# P04_POWER01.net
KiCad netlist of a schematic drawn in Altium Designer
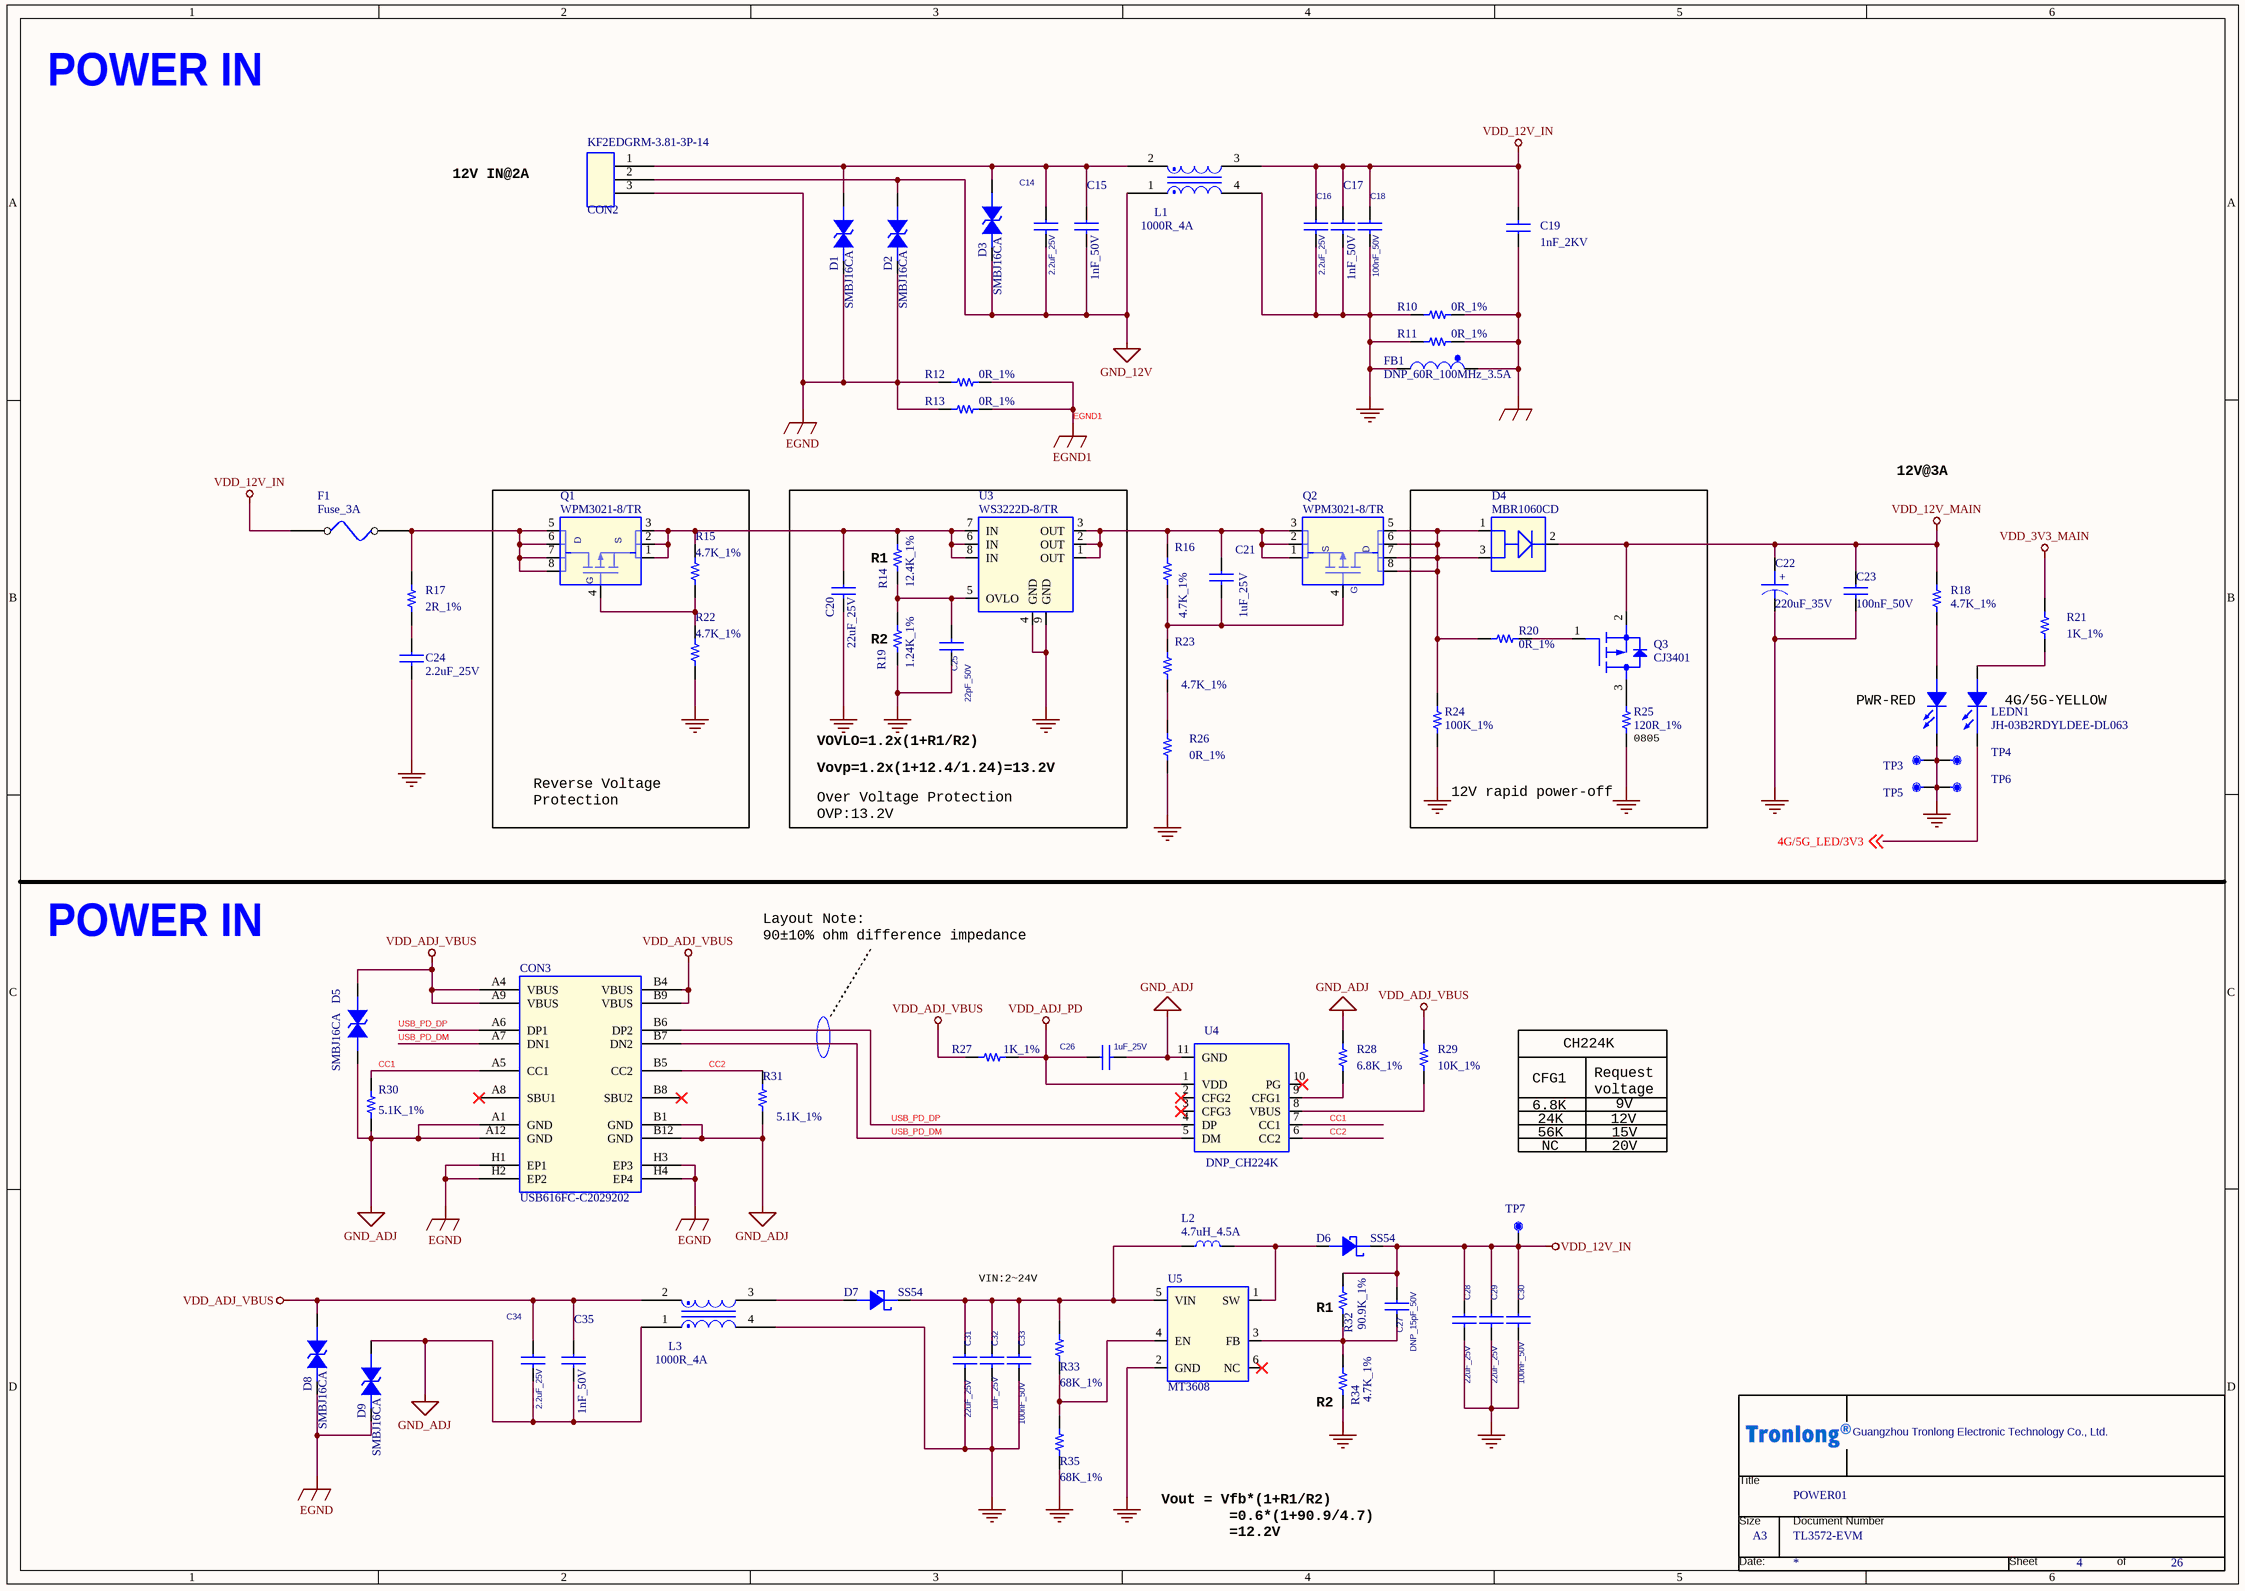
[diagram p0: P04_POWER01.SchDoc]

(export (version "E")
  (design (tool "Eeschema 10.0.6"))
  (components
    (comp (ref "C14")
      (value "2.2uF_25V")
      (footprint "C1206")
      (description "贴片陶瓷电容,2.2uF,10%,25V,X7R")
      (fields
        (field (name "MANUFACTURER") "广东风华高新科技股份有限公司（FH）")
        (field (name "MANUFACTURER PARTNUMBER") "1206B225K250NT")
      )
      (libsource (lib "*") (part "CAP NP_Dup2"))
    )
    (comp (ref "C15")
      (value "1nF_50V")
      (footprint "C0402")
      (description "贴片陶瓷电容,1nF,10%,50V,X7R")
      (fields
        (field (name "MANUFACTURER") "广东风华高新科技股份有限公司（FH）")
        (field (name "MANUFACTURER PARTNUMBER") "0402B102K500NT")
      )
      (libsource (lib "*") (part "CAP NP_Dup3"))
    )
    (comp (ref "C16")
      (value "2.2uF_25V")
      (footprint "C1206")
      (description "贴片陶瓷电容,2.2uF,10%,25V,X7R")
      (fields
        (field (name "MANUFACTURER") "广东风华高新科技股份有限公司（FH）")
        (field (name "MANUFACTURER PARTNUMBER") "1206B225K250NT")
      )
      (libsource (lib "*") (part "CAP NP_Dup2"))
    )
    (comp (ref "C17")
      (value "1nF_50V")
      (footprint "C0402")
      (description "贴片陶瓷电容,1nF,10%,50V,X7R")
      (fields
        (field (name "MANUFACTURER PARTNUMBER") "0402B102K500NT")
        (field (name "MANUFACTURER") "广东风华高新科技股份有限公司（FH）")
      )
      (libsource (lib "*") (part "CAP NP_Dup3"))
    )
    (comp (ref "C18")
      (value "100nF_50V")
      (footprint "C0402")
      (description "贴片陶瓷电容,100nF,10%,50V,X7R")
      (fields
        (field (name "MANUFACTURER PARTNUMBER") "0402B104K500NT")
        (field (name "MANUFACTURER") "广东风华高新科技股份有限公司（FH）")
      )
      (libsource (lib "*") (part "CAP_NP"))
    )
    (comp (ref "C19")
      (value "1nF_2KV")
      (footprint "C1206")
      (description "贴片陶瓷电容,1nF,10%,2KV,X7R")
      (fields
        (field (name "MANUFACTURER") "广东风华高新科技股份有限公司（FH）")
        (field (name "MANUFACTURER PARTNUMBER") "1206B102K202NT")
      )
      (libsource (lib "*") (part "CAP NP_Dup2"))
    )
    (comp (ref "C20")
      (value "22uF_25V")
      (footprint "C0805")
      (description "贴片陶瓷电容,22uF,20%,25V,X5R")
      (fields
        (field (name "MANUFACTURER") "广东风华高新科技股份有限公司（FH）")
        (field (name "MANUFACTURER PARTNUMBER") "0805X226M250NT")
      )
      (libsource (lib "*") (part "CAP NP_Dup2"))
    )
    (comp (ref "C21")
      (value "1uF_25V")
      (footprint "C0402")
      (description "贴片陶瓷电容,1uF,10%,25V,X5R")
      (fields
        (field (name "MANUFACTURER PARTNUMBER") "0402X105K250NT")
        (field (name "MANUFACTURER") "广东风华高新科技股份有限公司（FH）")
      )
      (libsource (lib "*") (part "CAP NP_Dup2"))
    )
    (comp (ref "C22")
      (value "220uF_35V")
      (footprint "cap_alu_smd_8x10d5")
      (description "贴片式铝电解电容,220uF,20%,35V")
      (fields
        (field (name "MANUFACTURER PARTNUMBER") "RVT1V221M0810VG")
        (field (name "MANUFACTURER") "东莞市合粤电子有限公司（Heyue）")
      )
      (libsource (lib "*") (part "CAP POL_Dup1"))
    )
    (comp (ref "C23")
      (value "100nF_50V")
      (footprint "C0402")
      (description "贴片陶瓷电容,100nF,10%,50V,X7R")
      (fields
        (field (name "MANUFACTURER PARTNUMBER") "0402B104K500NT")
        (field (name "MANUFACTURER") "广东风华高新科技股份有限公司（FH）")
      )
      (libsource (lib "*") (part "CAP NP_Dup2"))
    )
    (comp (ref "C24")
      (value "2.2uF_25V")
      (footprint "C1206")
      (description "贴片陶瓷电容,2.2uF,10%,25V,X7R")
      (fields
        (field (name "MANUFACTURER") "广东风华高新科技股份有限公司（FH）")
        (field (name "MANUFACTURER PARTNUMBER") "1206B225K250NT")
      )
      (libsource (lib "*") (part "CAP NP_Dup2"))
    )
    (comp (ref "C25")
      (value "22pF_50V")
      (footprint "C0603")
      (description "贴片陶瓷电容,22pF,5%,50V,COG")
      (fields
        (field (name "MANUFACTURER PARTNUMBER") "0603CG220J500NT")
        (field (name "MANUFACTURER") "广东风华高新科技股份有限公司（FH）")
      )
      (libsource (lib "*") (part "CAP NP_Dup2"))
    )
    (comp (ref "C26")
      (value "1uF_25V")
      (footprint "C0402")
      (description "贴片陶瓷电容,1uF,10%,25V,X5R")
      (fields
        (field (name "MANUFACTURER PARTNUMBER") "0402X105K250NT")
        (field (name "MANUFACTURER") "广东风华高新科技股份有限公司（FH）")
      )
      (libsource (lib "*") (part "CAP NP_Dup2"))
    )
    (comp (ref "C27")
      (value "DNP_15pF_50V")
      (footprint "C0402")
      (description "贴片陶瓷电容,15pF,5%,50V,COG")
      (fields
        (field (name "MANUFACTURER") "广东风华高新科技股份有限公司（FH）")
        (field (name "MANUFACTURER PARTNUMBER") "0402CG150J500NT")
      )
      (libsource (lib "*") (part "CAP NP_Dup2"))
    )
    (comp (ref "C28")
      (value "22uF_25V")
      (footprint "C0805")
      (description "贴片陶瓷电容,22uF,20%,25V,X5R")
      (fields
        (field (name "MANUFACTURER") "广东风华高新科技股份有限公司（FH）")
        (field (name "MANUFACTURER PARTNUMBER") "0805X226M250NT")
      )
      (libsource (lib "*") (part "CAP NP_Dup2"))
    )
    (comp (ref "C29")
      (value "22uF_25V")
      (footprint "C0805")
      (description "贴片陶瓷电容,22uF,20%,25V,X5R")
      (fields
        (field (name "MANUFACTURER") "广东风华高新科技股份有限公司（FH）")
        (field (name "MANUFACTURER PARTNUMBER") "0805X226M250NT")
      )
      (libsource (lib "*") (part "CAP NP_Dup2"))
    )
    (comp (ref "C30")
      (value "100nF_50V")
      (footprint "C0402")
      (description "贴片陶瓷电容,100nF,10%,50V,X7R")
      (fields
        (field (name "MANUFACTURER") "广东风华高新科技股份有限公司（FH）")
        (field (name "MANUFACTURER PARTNUMBER") "0402B104K500NT")
      )
      (libsource (lib "*") (part "CAP NP_Dup2"))
    )
    (comp (ref "C31")
      (value "22uF_25V")
      (footprint "C0805")
      (description "贴片陶瓷电容,22uF,20%,25V,X5R")
      (fields
        (field (name "MANUFACTURER") "广东风华高新科技股份有限公司（FH）")
        (field (name "MANUFACTURER PARTNUMBER") "0805X226M250NT")
      )
      (libsource (lib "*") (part "CAP NP_Dup2"))
    )
    (comp (ref "C32")
      (value "1uF_25V")
      (footprint "C0402")
      (description "贴片陶瓷电容,1uF,10%,25V,X5R")
      (fields
        (field (name "MANUFACTURER PARTNUMBER") "0402X105K250NT")
        (field (name "MANUFACTURER") "广东风华高新科技股份有限公司（FH）")
      )
      (libsource (lib "*") (part "CAP NP_Dup2"))
    )
    (comp (ref "C33")
      (value "100nF_50V")
      (footprint "C0402")
      (description "贴片陶瓷电容,100nF,10%,50V,X7R")
      (fields
        (field (name "MANUFACTURER PARTNUMBER") "0402B104K500NT")
        (field (name "MANUFACTURER") "广东风华高新科技股份有限公司（FH）")
      )
      (libsource (lib "*") (part "CAP NP_Dup2"))
    )
    (comp (ref "C34")
      (value "2.2uF_25V")
      (footprint "C1206")
      (description "贴片陶瓷电容,2.2uF,10%,25V,X7R")
      (fields
        (field (name "MANUFACTURER") "广东风华高新科技股份有限公司（FH）")
        (field (name "MANUFACTURER PARTNUMBER") "1206B225K250NT")
      )
      (libsource (lib "*") (part "CAP NP_Dup2"))
    )
    (comp (ref "C35")
      (value "1nF_50V")
      (footprint "C0402")
      (description "贴片陶瓷电容,1nF,10%,50V,X7R")
      (fields
        (field (name "MANUFACTURER") "广东风华高新科技股份有限公司（FH）")
        (field (name "MANUFACTURER PARTNUMBER") "0402B102K500NT")
      )
      (libsource (lib "*") (part "CAP NP_Dup3"))
    )
    (comp (ref "CON2")
      (value "KF2EDGRM-3.81-3P-14")
      (footprint "CON_3P_3D81_90_MALE_A")
      (description "插拔式端子座,1x3P,3.81mm,90度,带法兰")
      (fields (field (name "MANUFACTURER") "慈溪市科发电子有限公司（KEFA）"))
      (libsource (lib "*") (part "CON3_Dup1"))
    )
    (comp (ref "CON3")
      (value "USB616FC-C2029202")
      (footprint "TYPE-C_16P_180_SMD")
      (description "Type-C座,16P,0.8mm,母座,侧贴")
      (fields (field (name "MANUFACTURER") "深圳市爱特姆科技有限公司（ATOM）"))
      (libsource (lib "*") (part "usb 3_0.0 type-c female"))
    )
    (comp (ref "D1")
      (value "SMBJ16CA")
      (footprint "SMB")
      (description "TVS二极管,VRWM=16V,VBR=17.8V,一组,双向")
      (fields (field (name "MANUFACTURER") "江苏长晶科技有限公司（JSCJ）"))
      (libsource (lib "*") (part "DIODE-TRIG"))
    )
    (comp (ref "D2")
      (value "SMBJ16CA")
      (footprint "SMB")
      (description "TVS二极管,VRWM=16V,VBR=17.8V,一组,双向")
      (fields (field (name "MANUFACTURER") "江苏长晶科技有限公司（JSCJ）"))
      (libsource (lib "*") (part "DIODE-TRIG"))
    )
    (comp (ref "D3")
      (value "SMBJ16CA")
      (footprint "SMB")
      (description "TVS二极管,VRWM=16V,VBR=17.8V,一组,双向")
      (fields (field (name "MANUFACTURER") "江苏长晶科技有限公司（JSCJ）"))
      (libsource (lib "*") (part "DIODE-TRIG"))
    )
    (comp (ref "D4")
      (value "MBR1060CD")
      (footprint "TO-252")
      (description "肖特基二极管,VR=60V,IF=10A,VF=0.75V@5A,两路")
      (fields (field (name "MANUFACTURER") "山东芯诺电子科技股份有限公司（xnelec）"))
      (libsource (lib "*") (part "MBRB1045_0"))
    )
    (comp (ref "D5")
      (value "SMBJ16CA")
      (footprint "SMB")
      (description "TVS二极管,VRWM=16V,VBR=17.8V,一组,双向")
      (fields (field (name "MANUFACTURER") "江苏长晶科技股份有限公司（JSCJ）"))
      (libsource (lib "*") (part "DIODE-TRIG"))
    )
    (comp (ref "D6")
      (value "SS54")
      (footprint "SMA")
      (description "肖特基二极管,VR=40V,IF=5A,VF=0.55V@5A")
      (fields (field (name "MANUFACTURER") "江苏长晶科技股份有限公司（JSCJ）"))
      (libsource (lib "*") (part "DIODE SCHOTTKY"))
    )
    (comp (ref "D7")
      (value "SS54")
      (footprint "SMA")
      (description "肖特基二极管,VR=40V,IF=5A,VF=0.55V@5A")
      (fields (field (name "MANUFACTURER") "江苏长晶科技股份有限公司（JSCJ）"))
      (libsource (lib "*") (part "DIODE SCHOTTKY"))
    )
    (comp (ref "D8")
      (value "SMBJ16CA")
      (footprint "SMB")
      (description "TVS二极管,VRWM=16V,VBR=17.8V,一组,双向")
      (fields (field (name "MANUFACTURER") "江苏长晶科技有限公司（JSCJ）"))
      (libsource (lib "*") (part "DIODE-TRIG"))
    )
    (comp (ref "D9")
      (value "SMBJ16CA")
      (footprint "SMB")
      (description "TVS二极管,VRWM=16V,VBR=17.8V,一组,双向")
      (fields (field (name "MANUFACTURER") "江苏长晶科技有限公司（JSCJ）"))
      (libsource (lib "*") (part "DIODE-TRIG"))
    )
    (comp (ref "F1")
      (value "Fuse_3A")
      (footprint "F1206")
      (description "保险丝，Vmax=72V,Imax=50A,Ihold=3A")
      (fields
        (field (name "MANUFACTURER") "东莞市竞沃电子科技有限公司（TLC）")
        (field (name "MANUFACTURER PARTNUMBER") "F12T3")
      )
      (libsource (lib "*") (part "FUSE"))
    )
    (comp (ref "FB1")
      (value "DNP_60R_100MHz_3.5A")
      (footprint "L0603")
      (description "磁珠,20mΩ,3.5A,60R@100MHz")
      (fields
        (field (name "MANUFACTURER") "TDK(日本东电化)")
        (field (name "MANUFACTURER PARTNUMBER") "MPZ1608S600ATAH0")
      )
      (libsource (lib "*") (part "FERRITE BEAD_Dup1"))
    )
    (comp (ref "L1")
      (value "1000R_4A")
      (footprint "SMD-L9070M-4P")
      (description "贴片共模电感,13mΩ,4A,50V,1000Ω@100MHz")
      (fields (field (name "MANUFACTURER") "深圳市宏业兴电子有限公司（HONGYEX）") (field (name "PART NUMBER") "G11.00002"))
      (libsource (lib "*") (part "ACM1211-701-2PL-TL01"))
    )
    (comp (ref "L2")
      (value "4.7uH_4.5A")
      (footprint "SMD-L5452M-2P")
      (description "贴片功率电感,4.7uH,0.060Ω,Isat=5A,Irms=4.5A")
      (fields
        (field (name "MANUFACTURER") "深圳市长江微电科技有限公司（Cjiang）")
        (field (name "MANUFACTURER PARTNUMBER") "FXL0530-4R7M")
      )
      (libsource (lib "*") (part "1211_CHOKE_0"))
    )
    (comp (ref "L3")
      (value "1000R_4A")
      (footprint "SMD-L9070M-4P")
      (description "贴片共模电感,13mΩ,4A,50V,1000Ω@100MHz")
      (fields (field (name "MANUFACTURER") "深圳市宏业兴电子有限公司（HONGYEX）") (field (name "PART NUMBER") "G11.00002"))
      (libsource (lib "*") (part "ACM1211-701-2PL-TL01"))
    )
    (comp (ref "LEDN1")
      (value "JH-03B2RDYLDEE-DL063")
      (footprint "led-th_4p-l12d8-w4d6")
      (description "直插式发光二极管,绿色,带灯座")
      (fields
        (field (name "MANUFACTURER") "深圳市巨弘光电有限公司（JUHLIGHT）")
        (field (name "MANUFACTURER PARTNUMBER") "JH-03B2YG1E-DL")
      )
      (libsource (lib "*") (part "LED_4"))
    )
    (comp (ref "Q1")
      (value "WPM3021-8/TR")
      (footprint "PSOPSOP-8L")
      (description "MOSFET,P沟道,VDSS=-30V,VGSS=±25V,ID=-13A,PD=3.8W,VGS(th)=-3V")
      (fields (field (name "MANUFACTURER") "上海韦尔半导体股份有限公司（WILLSEMI）"))
      (libsource (lib "") (part "WPM3021_1"))
    )
    (comp (ref "Q2")
      (value "WPM3021-8/TR")
      (footprint "PSOPSOP-8L")
      (description "MOSFET,P沟道,VDSS=-30V,VGSS=±25V,ID=-13A,PD=3.8W,VGS(th)=-3V")
      (fields (field (name "MANUFACTURER") "上海韦尔半导体股份有限公司（WILLSEMI）"))
      (libsource (lib "*") (part "WPM3021"))
    )
    (comp (ref "Q3")
      (value "CJ3401")
      (footprint "SOT23-3")
      (description "MOSFET,P沟道,VDSS=-30V,VGSS=±12V,ID=-4.2A,PD=0.35W,VGS(th)=-1.3V")
      (fields (field (name "MANUFACTURER") "江苏长晶科技股份有限公司（JSCJ）"))
      (libsource (lib "*") (part "MOSFET P SOT"))
    )
    (comp (ref "R10")
      (value "0R_1%")
      (footprint "R1206")
      (description "贴片电阻,0R,±1%,1/4W")
      (fields
        (field (name "MANUFACTURER PARTNUMBER") "RS-06000FT")
        (field (name "MANUFACTURER") "广东风华高新科技股份有限公司（FH）")
      )
      (libsource (lib "*") (part "Resistor_Dup3"))
    )
    (comp (ref "R11")
      (value "0R_1%")
      (footprint "R1206")
      (description "贴片电阻,0R,±1%,1/4W")
      (fields
        (field (name "MANUFACTURER PARTNUMBER") "RS-06000FT")
        (field (name "MANUFACTURER") "广东风华高新科技股份有限公司（FH）")
      )
      (libsource (lib "*") (part "Resistor_Dup3"))
    )
    (comp (ref "R12")
      (value "0R_1%")
      (footprint "R1206")
      (description "贴片电阻,0R,±1%,1/4W")
      (fields
        (field (name "MANUFACTURER") "广东风华高新科技股份有限公司（FH）")
        (field (name "MANUFACTURER PARTNUMBER") "RS-06000FT")
      )
      (libsource (lib "*") (part "Resistor_Dup3"))
    )
    (comp (ref "R13")
      (value "0R_1%")
      (footprint "R1206")
      (description "贴片电阻,0R,±1%,1/4W")
      (fields
        (field (name "MANUFACTURER PARTNUMBER") "RS-06000FT")
        (field (name "MANUFACTURER") "广东风华高新科技股份有限公司（FH）")
      )
      (libsource (lib "*") (part "Resistor_Dup3"))
    )
    (comp (ref "R14")
      (value "12.4K_1%")
      (footprint "R0402")
      (description "0402WGF1242TCE")
      (fields
        (field (name "MANUFACTURER PARTNUMBER") "12.4K,±1%,R0402,≥1/16W")
        (field (name "MANUFACTURER") "广州创龙")
      )
      (libsource (lib "*") (part "Resistor_Dup3"))
    )
    (comp (ref "R15")
      (value "4.7K_1%")
      (footprint "R0402")
      (description "贴片电阻,4.7K,±1%,1/16W")
      (fields
        (field (name "MANUFACTURER PARTNUMBER") "RC-02K4701FT")
        (field (name "MANUFACTURER") "广东风华高新科技股份有限公司（FH）")
      )
      (libsource (lib "*") (part "Resistor_Dup3"))
    )
    (comp (ref "R16")
      (value "4.7K_1%")
      (footprint "R0402")
      (description "贴片电阻,4.7K,±1%,1/16W")
      (fields
        (field (name "MANUFACTURER PARTNUMBER") "RC-02K4701FT")
        (field (name "MANUFACTURER") "广东风华高新科技股份有限公司（FH）")
      )
      (libsource (lib "*") (part "Resistor_Dup3"))
    )
    (comp (ref "R17")
      (value "2R_1%")
      (footprint "R1210")
      (description "贴片电阻,2R,±1%,1/3W")
      (fields
        (field (name "MANUFACTURER PARTNUMBER") "RS-1210L2R00FT")
        (field (name "MANUFACTURER") "广东风华高新科技股份有限公司（FH）")
      )
      (libsource (lib "*") (part "Resistor_Dup3"))
    )
    (comp (ref "R18")
      (value "4.7K_1%")
      (footprint "R0402")
      (description "贴片电阻,4.7K,±1%,1/16W")
      (fields
        (field (name "MANUFACTURER") "广东风华高新科技股份有限公司（FH）")
        (field (name "MANUFACTURER PARTNUMBER") "RC-02K4701FT")
      )
      (libsource (lib "*") (part "Resistor_Dup3"))
    )
    (comp (ref "R19")
      (value "1.24K_1%")
      (footprint "R0402")
      (description "贴片电阻,1.24K,±1%,1/16W")
      (fields
        (field (name "MANUFACTURER") "广东风华高新科技股份有限公司（FH）")
        (field (name "MANUFACTURER PARTNUMBER") "RC-02K1241FT")
      )
      (libsource (lib "*") (part "Resistor_Dup3"))
    )
    (comp (ref "R20")
      (value "0R_1%")
      (footprint "R0402")
      (description "贴片电阻,0R,±1%,1/16W")
      (fields
        (field (name "MANUFACTURER") "广东风华高新科技股份有限公司（FH）")
        (field (name "MANUFACTURER PARTNUMBER") "RC-02000FT")
      )
      (libsource (lib "*") (part "Resistor_Dup3"))
    )
    (comp (ref "R21")
      (value "1K_1%")
      (footprint "R0603")
      (description "贴片电阻,1K,±1%,1/10W")
      (fields
        (field (name "MANUFACTURER") "广东风华高新科技股份有限公司（FH）")
        (field (name "MANUFACTURER PARTNUMBER") "RS-03K1001FT")
      )
      (libsource (lib "*") (part "Resistor_Dup3"))
    )
    (comp (ref "R22")
      (value "4.7K_1%")
      (footprint "R0402")
      (description "贴片电阻,4.7K,±1%,1/16W")
      (fields
        (field (name "MANUFACTURER") "广东风华高新科技股份有限公司（FH）")
        (field (name "MANUFACTURER PARTNUMBER") "RC-02K4701FT")
      )
      (libsource (lib "*") (part "Resistor_Dup3"))
    )
    (comp (ref "R23")
      (value "4.7K_1%")
      (footprint "R0402")
      (description "贴片电阻,4.7K,±1%,1/16W")
      (fields
        (field (name "MANUFACTURER") "广东风华高新科技股份有限公司（FH）")
        (field (name "MANUFACTURER PARTNUMBER") "RC-02K4701FT")
      )
      (libsource (lib "*") (part "Resistor_Dup3"))
    )
    (comp (ref "R24")
      (value "100K_1%")
      (footprint "R0402")
      (description "RC0402FR-07100KL,0402WGF1003TCE")
      (fields
        (field (name "MANUFACTURER") "广州创龙")
        (field (name "MANUFACTURER PARTNUMBER") "100K,±1%,R0402,≥1/16W")
      )
      (libsource (lib "*") (part "Resistor_Dup3"))
    )
    (comp (ref "R25")
      (value "120R_1%")
      (footprint "R0805")
      (description "贴片电阻,120R,±1%,1/8W")
      (fields
        (field (name "MANUFACTURER") "广东风华高新科技股份有限公司（FH）")
        (field (name "MANUFACTURER PARTNUMBER") "RS-05K1200FT")
      )
      (libsource (lib "*") (part "Resistor_Dup3"))
    )
    (comp (ref "R26")
      (value "0R_1%")
      (footprint "R0402")
      (description "贴片电阻,0R,±1%,1/16W")
      (fields
        (field (name "MANUFACTURER") "广东风华高新科技股份有限公司（FH）")
        (field (name "MANUFACTURER PARTNUMBER") "RC-02000FT")
      )
      (libsource (lib "*") (part "Resistor_Dup3"))
    )
    (comp (ref "R27")
      (value "1K_1%")
      (footprint "R0805")
      (description "贴片电阻,1K,±1%,1/8W")
      (fields
        (field (name "MANUFACTURER PARTNUMBER") "RS-05K1001FT")
        (field (name "MANUFACTURER") "广东风华高新科技股份有限公司（FH）")
      )
      (libsource (lib "*") (part "Resistor_Dup3"))
    )
    (comp (ref "R28")
      (value "6.8K_1%")
      (footprint "R0402")
      (description "贴片电阻,6.8K,±1%,1/16W")
      (fields
        (field (name "MANUFACTURER") "广东风华高新科技股份有限公司（FH）")
        (field (name "MANUFACTURER PARTNUMBER") "RC-02K6801FT")
      )
      (libsource (lib "*") (part "Resistor_Dup3"))
    )
    (comp (ref "R29")
      (value "10K_1%")
      (footprint "R0402")
      (description "贴片电阻,10K,±1%,1/16W")
      (fields
        (field (name "MANUFACTURER") "广东风华高新科技股份有限公司（FH）")
        (field (name "MANUFACTURER PARTNUMBER") "RC-02K1002FT")
      )
      (libsource (lib "*") (part "Resistor_Dup3"))
    )
    (comp (ref "R30")
      (value "5.1K_1%")
      (footprint "R0402")
      (description "贴片电阻,5.1K,±1%,1/16W")
      (fields
        (field (name "MANUFACTURER") "广东风华高新科技股份有限公司（FH）")
        (field (name "MANUFACTURER PARTNUMBER") "RC-02K5101FT")
      )
      (libsource (lib "*") (part "Resistor_Dup3"))
    )
    (comp (ref "R31")
      (value "5.1K_1%")
      (footprint "R0402")
      (description "贴片电阻,5.1K,±1%,1/16W")
      (fields
        (field (name "MANUFACTURER") "广东风华高新科技股份有限公司（FH）")
        (field (name "MANUFACTURER PARTNUMBER") "RC-02K5101FT")
      )
      (libsource (lib "*") (part "Resistor_Dup3"))
    )
    (comp (ref "R32")
      (value "90.9K_1%")
      (footprint "R0402")
      (description "贴片电阻,90.9K,±1%,1/16W")
      (fields
        (field (name "MANUFACTURER") "广东风华高新科技股份有限公司（FH）")
        (field (name "MANUFACTURER PARTNUMBER") "RC-02K9092FT")
      )
      (libsource (lib "*") (part "Resistor_Dup3"))
    )
    (comp (ref "R33")
      (value "68K_1%")
      (footprint "R0402")
      (description "贴片电阻,68K,±1%,1/16W")
      (fields
        (field (name "MANUFACTURER PARTNUMBER") "RC-02K6802FT")
        (field (name "MANUFACTURER") "广东风华高新科技股份有限公司（FH）")
      )
      (libsource (lib "*") (part "Resistor_Dup3"))
    )
    (comp (ref "R34")
      (value "4.7K_1%")
      (footprint "R0402")
      (description "贴片电阻,4.7K,±1%,1/16W")
      (fields
        (field (name "MANUFACTURER PARTNUMBER") "RC-02K4701FT")
        (field (name "MANUFACTURER") "广东风华高新科技股份有限公司（FH）")
      )
      (libsource (lib "*") (part "Resistor_Dup3"))
    )
    (comp (ref "R35")
      (value "68K_1%")
      (footprint "R0402")
      (description "贴片电阻,68K,±1%,1/16W")
      (fields
        (field (name "MANUFACTURER") "广东风华高新科技股份有限公司（FH）")
        (field (name "MANUFACTURER PARTNUMBER") "RC-02K6802FT")
      )
      (libsource (lib "*") (part "Resistor_Dup3"))
    )
    (comp (ref "TP3")
      (value "TP-5011")
      (footprint "TP_DIP")
      (description "黑色直插测试柱")
      (fields (field (name "MANUFACTURER") "深圳市保定五金塑胶有限公司"))
      (libsource (lib "*") (part "TP-S40"))
    )
    (comp (ref "TP4")
      (value "TP-5011")
      (footprint "TP_DIP")
      (description "黑色直插测试柱")
      (fields (field (name "MANUFACTURER") "深圳市保定五金塑胶有限公司"))
      (libsource (lib "*") (part "TP-S40"))
    )
    (comp (ref "TP5")
      (value "TP-5011")
      (footprint "TP_DIP")
      (description "黑色直插测试柱")
      (fields (field (name "MANUFACTURER") "深圳市保定五金塑胶有限公司"))
      (libsource (lib "*") (part "TP-S40"))
    )
    (comp (ref "TP6")
      (value "TP-5011")
      (footprint "TP_DIP")
      (description "黑色直插测试柱")
      (fields (field (name "MANUFACTURER") "深圳市保定五金塑胶有限公司"))
      (libsource (lib "*") (part "TP-S40"))
    )
    (comp (ref "TP7")
      (value "SMT TP")
      (footprint "TP30")
      (description "/")
      (libsource (lib "*") (part "TP-S40"))
    )
    (comp (ref "U3")
      (value "WS3222D-8/TR")
      (footprint "DFN2x2-8L")
      (description "过压保护开关,VCC=2.5V~28V,过压保护阈值4V~15V可调")
      (fields (field (name "MANUFACTURER") "上海韦尔半导体股份有限公司（WILLSEMI）"))
      (libsource (lib "*") (part "WS3222D-8/TR"))
    )
    (comp (ref "U4")
      (value "DNP_CH224K")
      (footprint "ESSOP-10")
      (description "USB Type-C PD 受电芯片")
      (fields
        (field (name "MANUFACTURER PARTNUMBER") "CH224K")
        (field (name "MANUFACTURER") "南京沁恒微电子股份有限公司（WCH）")
      )
      (libsource (lib "*") (part "CH224K"))
    )
    (comp (ref "U5")
      (value "MT3608")
      (footprint "SOT-23-6L")
      (description "DC/DC,Boost,Vin:2V~24V,Vout:2V~28V,4A,1路")
      (fields (field (name "MANUFACTURER") "西安航天民芯科技有限公司(aerosemi)"))
      (libsource (lib "*") (part "WD1304E30_17"))
    )
  )
  (nets
    (net (code "1") (name "/CC1") (class "Default")
      (node (ref "CON3") (pin "A5") (pinfunction "CC1_A5") (pintype "passive"))
      (node (ref "R30") (pin "1") (pinfunction "1_1") (pintype "passive"))
      (node (ref "U4") (pin "7") (pinfunction "CC1_7") (pintype "passive"))
    )
    (net (code "2") (name "/CC2") (class "Default")
      (node (ref "CON3") (pin "B5") (pinfunction "CC2_B5") (pintype "passive"))
      (node (ref "R31") (pin "1") (pinfunction "1_1") (pintype "passive"))
      (node (ref "U4") (pin "6") (pinfunction "CC2_6") (pintype "passive"))
    )
    (net (code "3") (name "/USB_PD_DM") (class "Default")
      (node (ref "CON3") (pin "A7") (pinfunction "DN1_A7") (pintype "passive"))
      (node (ref "CON3") (pin "B7") (pinfunction "DN2_B7") (pintype "passive"))
      (node (ref "U4") (pin "5") (pinfunction "DM_5") (pintype "passive"))
    )
    (net (code "4") (name "/USB_PD_DP") (class "Default")
      (node (ref "CON3") (pin "A6") (pinfunction "DP1_A6") (pintype "passive"))
      (node (ref "CON3") (pin "B6") (pinfunction "DP2_B6") (pintype "passive"))
      (node (ref "U4") (pin "4") (pinfunction "DP_4") (pintype "passive"))
    )
    (net (code "5") (name "4G{slash}5G_LED{slash}3V3") (class "Default")
      (node (ref "LEDN1") (pin "4") (pinfunction "CATHODE2_4") (pintype "passive"))
    )
    (net (code "6") (name "EGND") (class "Default")
      (node (ref "C19") (pin "1") (pinfunction "1_1") (pintype "passive"))
      (node (ref "CON2") (pin "3") (pinfunction "3_3") (pintype "passive"))
      (node (ref "CON3") (pin "H1") (pinfunction "EP1_H1") (pintype "power_in"))
      (node (ref "CON3") (pin "H2") (pinfunction "EP2_H2") (pintype "power_in"))
      (node (ref "CON3") (pin "H3") (pinfunction "EP3_H3") (pintype "power_in"))
      (node (ref "CON3") (pin "H4") (pinfunction "EP4_H4") (pintype "power_in"))
      (node (ref "D1") (pin "1") (pinfunction "1_1") (pintype "passive"))
      (node (ref "D2") (pin "1") (pinfunction "1_1") (pintype "passive"))
      (node (ref "D8") (pin "1") (pinfunction "1_1") (pintype "passive"))
      (node (ref "D9") (pin "1") (pinfunction "1_1") (pintype "passive"))
      (node (ref "FB1") (pin "1") (pinfunction "1_1") (pintype "passive"))
      (node (ref "R10") (pin "2") (pinfunction "2_2") (pintype "passive"))
      (node (ref "R11") (pin "2") (pinfunction "2_2") (pintype "passive"))
      (node (ref "R12") (pin "1") (pinfunction "1_1") (pintype "passive"))
      (node (ref "R13") (pin "1") (pinfunction "1_1") (pintype "passive"))
    )
    (net (code "7") (name "EGND1") (class "Default")
      (node (ref "R12") (pin "2") (pinfunction "2_2") (pintype "passive"))
      (node (ref "R13") (pin "2") (pinfunction "2_2") (pintype "passive"))
    )
    (net (code "8") (name "GND") (class "Default")
      (node (ref "C16") (pin "2") (pinfunction "2_2") (pintype "passive"))
      (node (ref "C17") (pin "2") (pinfunction "2_2") (pintype "passive"))
      (node (ref "C18") (pin "2") (pinfunction "2_2") (pintype "passive"))
      (node (ref "C20") (pin "2") (pinfunction "2_2") (pintype "passive"))
      (node (ref "C22") (pin "2") (pinfunction "2_2") (pintype "passive"))
      (node (ref "C23") (pin "2") (pinfunction "2_2") (pintype "passive"))
      (node (ref "C24") (pin "2") (pinfunction "2_2") (pintype "passive"))
      (node (ref "C25") (pin "1") (pinfunction "1_1") (pintype "passive"))
      (node (ref "C28") (pin "2") (pinfunction "2_2") (pintype "passive"))
      (node (ref "C29") (pin "2") (pinfunction "2_2") (pintype "passive"))
      (node (ref "C30") (pin "2") (pinfunction "2_2") (pintype "passive"))
      (node (ref "C31") (pin "2") (pinfunction "2_2") (pintype "passive"))
      (node (ref "C32") (pin "2") (pinfunction "2_2") (pintype "passive"))
      (node (ref "C33") (pin "2") (pinfunction "2_2") (pintype "passive"))
      (node (ref "FB1") (pin "2") (pinfunction "2_2") (pintype "passive"))
      (node (ref "L1") (pin "4") (pinfunction "4_4") (pintype "passive"))
      (node (ref "L3") (pin "4") (pinfunction "4_4") (pintype "passive"))
      (node (ref "LEDN1") (pin "1") (pinfunction "CATHODE1_1") (pintype "passive"))
      (node (ref "R10") (pin "1") (pinfunction "1_1") (pintype "passive"))
      (node (ref "R11") (pin "1") (pinfunction "1_1") (pintype "passive"))
      (node (ref "R19") (pin "2") (pinfunction "2_2") (pintype "passive"))
      (node (ref "R22") (pin "1") (pinfunction "1_1") (pintype "passive"))
      (node (ref "R24") (pin "1") (pinfunction "1_1") (pintype "passive"))
      (node (ref "R25") (pin "2") (pinfunction "2_2") (pintype "passive"))
      (node (ref "R26") (pin "2") (pinfunction "2_2") (pintype "passive"))
      (node (ref "R34") (pin "1") (pinfunction "1_1") (pintype "passive"))
      (node (ref "R35") (pin "1") (pinfunction "1_1") (pintype "passive"))
      (node (ref "TP3") (pin "1") (pinfunction "1_1") (pintype "passive"))
      (node (ref "TP4") (pin "1") (pinfunction "1_1") (pintype "passive"))
      (node (ref "TP5") (pin "1") (pinfunction "1_1") (pintype "passive"))
      (node (ref "TP6") (pin "1") (pinfunction "1_1") (pintype "passive"))
      (node (ref "U3") (pin "4") (pinfunction "GND_4") (pintype "power_in"))
      (node (ref "U3") (pin "9") (pinfunction "GND_9") (pintype "power_in"))
      (node (ref "U5") (pin "2") (pinfunction "GND_2") (pintype "power_in"))
    )
    (net (code "9") (name "GND_12V") (class "Default")
      (node (ref "C14") (pin "2") (pinfunction "2_2") (pintype "passive"))
      (node (ref "C15") (pin "2") (pinfunction "2_2") (pintype "passive"))
      (node (ref "CON2") (pin "2") (pinfunction "2_2") (pintype "passive"))
      (node (ref "D2") (pin "2") (pinfunction "2_2") (pintype "passive"))
      (node (ref "D3") (pin "1") (pinfunction "1_1") (pintype "passive"))
      (node (ref "L1") (pin "1") (pinfunction "1_1") (pintype "passive"))
    )
    (net (code "10") (name "GND_ADJ") (class "Default")
      (node (ref "C26") (pin "2") (pinfunction "2_2") (pintype "passive"))
      (node (ref "C34") (pin "2") (pinfunction "2_2") (pintype "passive"))
      (node (ref "C35") (pin "2") (pinfunction "2_2") (pintype "passive"))
      (node (ref "CON3") (pin "A1") (pinfunction "GND_A1") (pintype "power_in"))
      (node (ref "CON3") (pin "A12") (pinfunction "GND_A12") (pintype "power_in"))
      (node (ref "CON3") (pin "B1") (pinfunction "GND_B1") (pintype "power_in"))
      (node (ref "CON3") (pin "B12") (pinfunction "GND_B12") (pintype "power_in"))
      (node (ref "D5") (pin "1") (pinfunction "1_1") (pintype "passive"))
      (node (ref "D9") (pin "2") (pinfunction "2_2") (pintype "passive"))
      (node (ref "L3") (pin "1") (pinfunction "1_1") (pintype "passive"))
      (node (ref "R28") (pin "1") (pinfunction "1_1") (pintype "passive"))
      (node (ref "R30") (pin "2") (pinfunction "2_2") (pintype "passive"))
      (node (ref "R31") (pin "2") (pinfunction "2_2") (pintype "passive"))
      (node (ref "U4") (pin "11") (pinfunction "GND_11") (pintype "power_in"))
    )
    (net (code "11") (name "Net-(C14-Pad1)") (class "Default")
      (node (ref "C14") (pin "1") (pinfunction "1_1") (pintype "passive"))
      (node (ref "C15") (pin "1") (pinfunction "1_1") (pintype "passive"))
      (node (ref "CON2") (pin "1") (pinfunction "1_1") (pintype "passive"))
      (node (ref "D1") (pin "2") (pinfunction "2_2") (pintype "passive"))
      (node (ref "D3") (pin "2") (pinfunction "2_2") (pintype "passive"))
      (node (ref "L1") (pin "2") (pinfunction "2_2") (pintype "passive"))
    )
    (net (code "12") (name "Net-(C24-Pad1)") (class "Default")
      (node (ref "C24") (pin "1") (pinfunction "1_1") (pintype "passive"))
      (node (ref "R17") (pin "1") (pinfunction "1_1") (pintype "passive"))
    )
    (net (code "13") (name "Net-(D6-ANODE)") (class "Default")
      (node (ref "D6") (pin "1") (pinfunction "ANODE_1") (pintype "passive"))
      (node (ref "L2") (pin "2") (pinfunction "2_2") (pintype "passive"))
      (node (ref "U5") (pin "1") (pinfunction "SW_1") (pintype "power_in"))
    )
    (net (code "14") (name "Net-(D7-ANODE)") (class "Default")
      (node (ref "D7") (pin "1") (pinfunction "ANODE_1") (pintype "passive"))
      (node (ref "L3") (pin "3") (pinfunction "3_3") (pintype "passive"))
    )
    (net (code "15") (name "Net-(D7-CATHODE)") (class "Default")
      (node (ref "C31") (pin "1") (pinfunction "1_1") (pintype "passive"))
      (node (ref "C32") (pin "1") (pinfunction "1_1") (pintype "passive"))
      (node (ref "C33") (pin "1") (pinfunction "1_1") (pintype "passive"))
      (node (ref "D7") (pin "2") (pinfunction "CATHODE_2") (pintype "passive"))
      (node (ref "L2") (pin "1") (pinfunction "1_1") (pintype "passive"))
      (node (ref "R33") (pin "2") (pinfunction "2_2") (pintype "passive"))
      (node (ref "U5") (pin "5") (pinfunction "VIN_5") (pintype "passive"))
    )
    (net (code "16") (name "Net-(LEDN1-ANODE1)") (class "Default")
      (node (ref "LEDN1") (pin "2") (pinfunction "ANODE1_2") (pintype "passive"))
      (node (ref "R18") (pin "2") (pinfunction "2_2") (pintype "passive"))
    )
    (net (code "17") (name "Net-(LEDN1-ANODE2)") (class "Default")
      (node (ref "LEDN1") (pin "3") (pinfunction "ANODE2_3") (pintype "passive"))
      (node (ref "R21") (pin "1") (pinfunction "1_1") (pintype "passive"))
    )
    (net (code "18") (name "Net-(Q1-D1)") (class "Default")
      (node (ref "F1") (pin "2") (pinfunction "2_2") (pintype "passive"))
      (node (ref "Q1") (pin "5") (pinfunction "D1_5") (pintype "passive"))
      (node (ref "Q1") (pin "6") (pinfunction "D2_6") (pintype "passive"))
      (node (ref "Q1") (pin "7") (pinfunction "D3_7") (pintype "passive"))
      (node (ref "Q1") (pin "8") (pinfunction "D4_8") (pintype "passive"))
      (node (ref "R17") (pin "2") (pinfunction "2_2") (pintype "passive"))
    )
    (net (code "19") (name "Net-(Q1-G)") (class "Default")
      (node (ref "Q1") (pin "4") (pinfunction "G_4") (pintype "passive"))
      (node (ref "R15") (pin "1") (pinfunction "1_1") (pintype "passive"))
      (node (ref "R22") (pin "2") (pinfunction "2_2") (pintype "passive"))
    )
    (net (code "20") (name "Net-(Q1-S1)") (class "Default")
      (node (ref "C20") (pin "1") (pinfunction "1_1") (pintype "passive"))
      (node (ref "Q1") (pin "1") (pinfunction "S1_1") (pintype "passive"))
      (node (ref "Q1") (pin "2") (pinfunction "S2_2") (pintype "passive"))
      (node (ref "Q1") (pin "3") (pinfunction "S3_3") (pintype "passive"))
      (node (ref "R14") (pin "1") (pinfunction "1_1") (pintype "passive"))
      (node (ref "R15") (pin "2") (pinfunction "2_2") (pintype "passive"))
      (node (ref "U3") (pin "6") (pinfunction "IN_6") (pintype "power_in"))
      (node (ref "U3") (pin "7") (pinfunction "IN_7") (pintype "power_in"))
      (node (ref "U3") (pin "8") (pinfunction "IN_8") (pintype "power_in"))
    )
    (net (code "21") (name "Net-(Q2-D1)") (class "Default")
      (node (ref "D4") (pin "1") (pinfunction "1_1") (pintype "passive"))
      (node (ref "D4") (pin "3") (pinfunction "3_3") (pintype "passive"))
      (node (ref "Q2") (pin "5") (pinfunction "D1_5") (pintype "passive"))
      (node (ref "Q2") (pin "6") (pinfunction "D2_6") (pintype "passive"))
      (node (ref "Q2") (pin "7") (pinfunction "D3_7") (pintype "passive"))
      (node (ref "Q2") (pin "8") (pinfunction "D4_8") (pintype "passive"))
      (node (ref "R20") (pin "2") (pinfunction "2_2") (pintype "passive"))
      (node (ref "R24") (pin "2") (pinfunction "2_2") (pintype "passive"))
    )
    (net (code "22") (name "Net-(Q2-G)") (class "Default")
      (node (ref "C21") (pin "2") (pinfunction "2_2") (pintype "passive"))
      (node (ref "Q2") (pin "4") (pinfunction "G_4") (pintype "passive"))
      (node (ref "R16") (pin "1") (pinfunction "1_1") (pintype "passive"))
      (node (ref "R23") (pin "2") (pinfunction "2_2") (pintype "passive"))
    )
    (net (code "23") (name "Net-(Q2-S1)") (class "Default")
      (node (ref "C21") (pin "1") (pinfunction "1_1") (pintype "passive"))
      (node (ref "Q2") (pin "1") (pinfunction "S1_1") (pintype "passive"))
      (node (ref "Q2") (pin "2") (pinfunction "S2_2") (pintype "passive"))
      (node (ref "Q2") (pin "3") (pinfunction "S3_3") (pintype "passive"))
      (node (ref "R16") (pin "2") (pinfunction "2_2") (pintype "passive"))
      (node (ref "U3") (pin "1") (pinfunction "OUT_1") (pintype "power_in"))
      (node (ref "U3") (pin "2") (pinfunction "OUT_2") (pintype "power_in"))
      (node (ref "U3") (pin "3") (pinfunction "OUT_3") (pintype "power_in"))
    )
    (net (code "24") (name "Net-(Q3-DRAIN)") (class "Default")
      (node (ref "Q3") (pin "3") (pinfunction "DRAIN_3") (pintype "passive"))
      (node (ref "R25") (pin "1") (pinfunction "1_1") (pintype "passive"))
    )
    (net (code "25") (name "Net-(Q3-GATE)") (class "Default")
      (node (ref "Q3") (pin "1") (pinfunction "GATE_1") (pintype "passive"))
      (node (ref "R20") (pin "1") (pinfunction "1_1") (pintype "passive"))
    )
    (net (code "26") (name "Net-(R23-Pad1)") (class "Default")
      (node (ref "R23") (pin "1") (pinfunction "1_1") (pintype "passive"))
      (node (ref "R26") (pin "1") (pinfunction "1_1") (pintype "passive"))
    )
    (net (code "27") (name "Net-(U3-OVLO)") (class "Default")
      (node (ref "C25") (pin "2") (pinfunction "2_2") (pintype "passive"))
      (node (ref "R14") (pin "2") (pinfunction "2_2") (pintype "passive"))
      (node (ref "R19") (pin "1") (pinfunction "1_1") (pintype "passive"))
      (node (ref "U3") (pin "5") (pinfunction "OVLO_5") (pintype "passive"))
    )
    (net (code "28") (name "Net-(U4-CFG1)") (class "Default")
      (node (ref "R28") (pin "2") (pinfunction "2_2") (pintype "passive"))
      (node (ref "U4") (pin "9") (pinfunction "CFG1_9") (pintype "passive"))
    )
    (net (code "29") (name "Net-(U4-VBUS)") (class "Default")
      (node (ref "R29") (pin "2") (pinfunction "2_2") (pintype "passive"))
      (node (ref "U4") (pin "8") (pinfunction "VBUS_8") (pintype "passive"))
    )
    (net (code "30") (name "Net-(U5-EN)") (class "Default")
      (node (ref "R33") (pin "1") (pinfunction "1_1") (pintype "passive"))
      (node (ref "R35") (pin "2") (pinfunction "2_2") (pintype "passive"))
      (node (ref "U5") (pin "4") (pinfunction "EN_4") (pintype "passive"))
    )
    (net (code "31") (name "Net-(U5-FB)") (class "Default")
      (node (ref "C27") (pin "2") (pinfunction "2_2") (pintype "passive"))
      (node (ref "R32") (pin "1") (pinfunction "1_1") (pintype "passive"))
      (node (ref "R34") (pin "2") (pinfunction "2_2") (pintype "passive"))
      (node (ref "U5") (pin "3") (pinfunction "FB_3") (pintype "passive"))
    )
    (net (code "32") (name "VDD_3V3_MAIN") (class "Default")
      (node (ref "R21") (pin "2") (pinfunction "2_2") (pintype "passive"))
    )
    (net (code "33") (name "VDD_12V_IN") (class "Default")
      (node (ref "C16") (pin "1") (pinfunction "1_1") (pintype "passive"))
      (node (ref "C17") (pin "1") (pinfunction "1_1") (pintype "passive"))
      (node (ref "C18") (pin "1") (pinfunction "1_1") (pintype "passive"))
      (node (ref "C19") (pin "2") (pinfunction "2_2") (pintype "passive"))
      (node (ref "C27") (pin "1") (pinfunction "1_1") (pintype "passive"))
      (node (ref "C28") (pin "1") (pinfunction "1_1") (pintype "passive"))
      (node (ref "C29") (pin "1") (pinfunction "1_1") (pintype "passive"))
      (node (ref "C30") (pin "1") (pinfunction "1_1") (pintype "passive"))
      (node (ref "D6") (pin "2") (pinfunction "CATHODE_2") (pintype "passive"))
      (node (ref "F1") (pin "1") (pinfunction "1_1") (pintype "passive"))
      (node (ref "L1") (pin "3") (pinfunction "3_3") (pintype "passive"))
      (node (ref "R32") (pin "2") (pinfunction "2_2") (pintype "passive"))
      (node (ref "TP7") (pin "1") (pinfunction "1_1") (pintype "passive"))
    )
    (net (code "34") (name "VDD_12V_MAIN") (class "Default")
      (node (ref "C22") (pin "1") (pinfunction "1_1") (pintype "passive"))
      (node (ref "C23") (pin "1") (pinfunction "1_1") (pintype "passive"))
      (node (ref "D4") (pin "2") (pinfunction "2_2") (pintype "passive"))
      (node (ref "Q3") (pin "2") (pinfunction "SOURCE_2") (pintype "passive"))
      (node (ref "R18") (pin "1") (pinfunction "1_1") (pintype "passive"))
    )
    (net (code "35") (name "VDD_ADJ_PD") (class "Default")
      (node (ref "C26") (pin "1") (pinfunction "1_1") (pintype "passive"))
      (node (ref "R27") (pin "1") (pinfunction "1_1") (pintype "passive"))
      (node (ref "U4") (pin "1") (pinfunction "VDD_1") (pintype "power_in"))
    )
    (net (code "36") (name "VDD_ADJ_VBUS") (class "Default")
      (node (ref "C34") (pin "1") (pinfunction "1_1") (pintype "passive"))
      (node (ref "C35") (pin "1") (pinfunction "1_1") (pintype "passive"))
      (node (ref "CON3") (pin "A4") (pinfunction "VBUS_A4") (pintype "power_in"))
      (node (ref "CON3") (pin "A9") (pinfunction "VBUS_A9") (pintype "power_in"))
      (node (ref "CON3") (pin "B4") (pinfunction "VBUS_B4") (pintype "power_in"))
      (node (ref "CON3") (pin "B9") (pinfunction "VBUS_B9") (pintype "power_in"))
      (node (ref "D5") (pin "2") (pinfunction "2_2") (pintype "passive"))
      (node (ref "D8") (pin "2") (pinfunction "2_2") (pintype "passive"))
      (node (ref "L3") (pin "2") (pinfunction "2_2") (pintype "passive"))
      (node (ref "R27") (pin "2") (pinfunction "2_2") (pintype "passive"))
      (node (ref "R29") (pin "1") (pinfunction "1_1") (pintype "passive"))
    )
    (net (code "37") (name "unconnected-(CON3-SBU1-PadA8)") (class "Default")
      (node (ref "CON3") (pin "A8") (pinfunction "SBU1_A8") (pintype "passive+no_connect"))
    )
    (net (code "38") (name "unconnected-(CON3-SBU2-PadB8)") (class "Default")
      (node (ref "CON3") (pin "B8") (pinfunction "SBU2_B8") (pintype "passive+no_connect"))
    )
    (net (code "39") (name "unconnected-(U4-CFG2-Pad2)") (class "Default")
      (node (ref "U4") (pin "2") (pinfunction "CFG2_2") (pintype "passive+no_connect"))
    )
    (net (code "40") (name "unconnected-(U4-CFG3-Pad3)") (class "Default")
      (node (ref "U4") (pin "3") (pinfunction "CFG3_3") (pintype "passive+no_connect"))
    )
    (net (code "41") (name "unconnected-(U4-PG-Pad10)") (class "Default")
      (node (ref "U4") (pin "10") (pinfunction "PG_10") (pintype "passive+no_connect"))
    )
    (net (code "42") (name "unconnected-(U5-NC-Pad6)") (class "Default")
      (node (ref "U5") (pin "6") (pinfunction "NC_6") (pintype "passive+no_connect"))
    )
  )
)
